# pga.net
KiCad netlist of a schematic drawn in Altium Designer
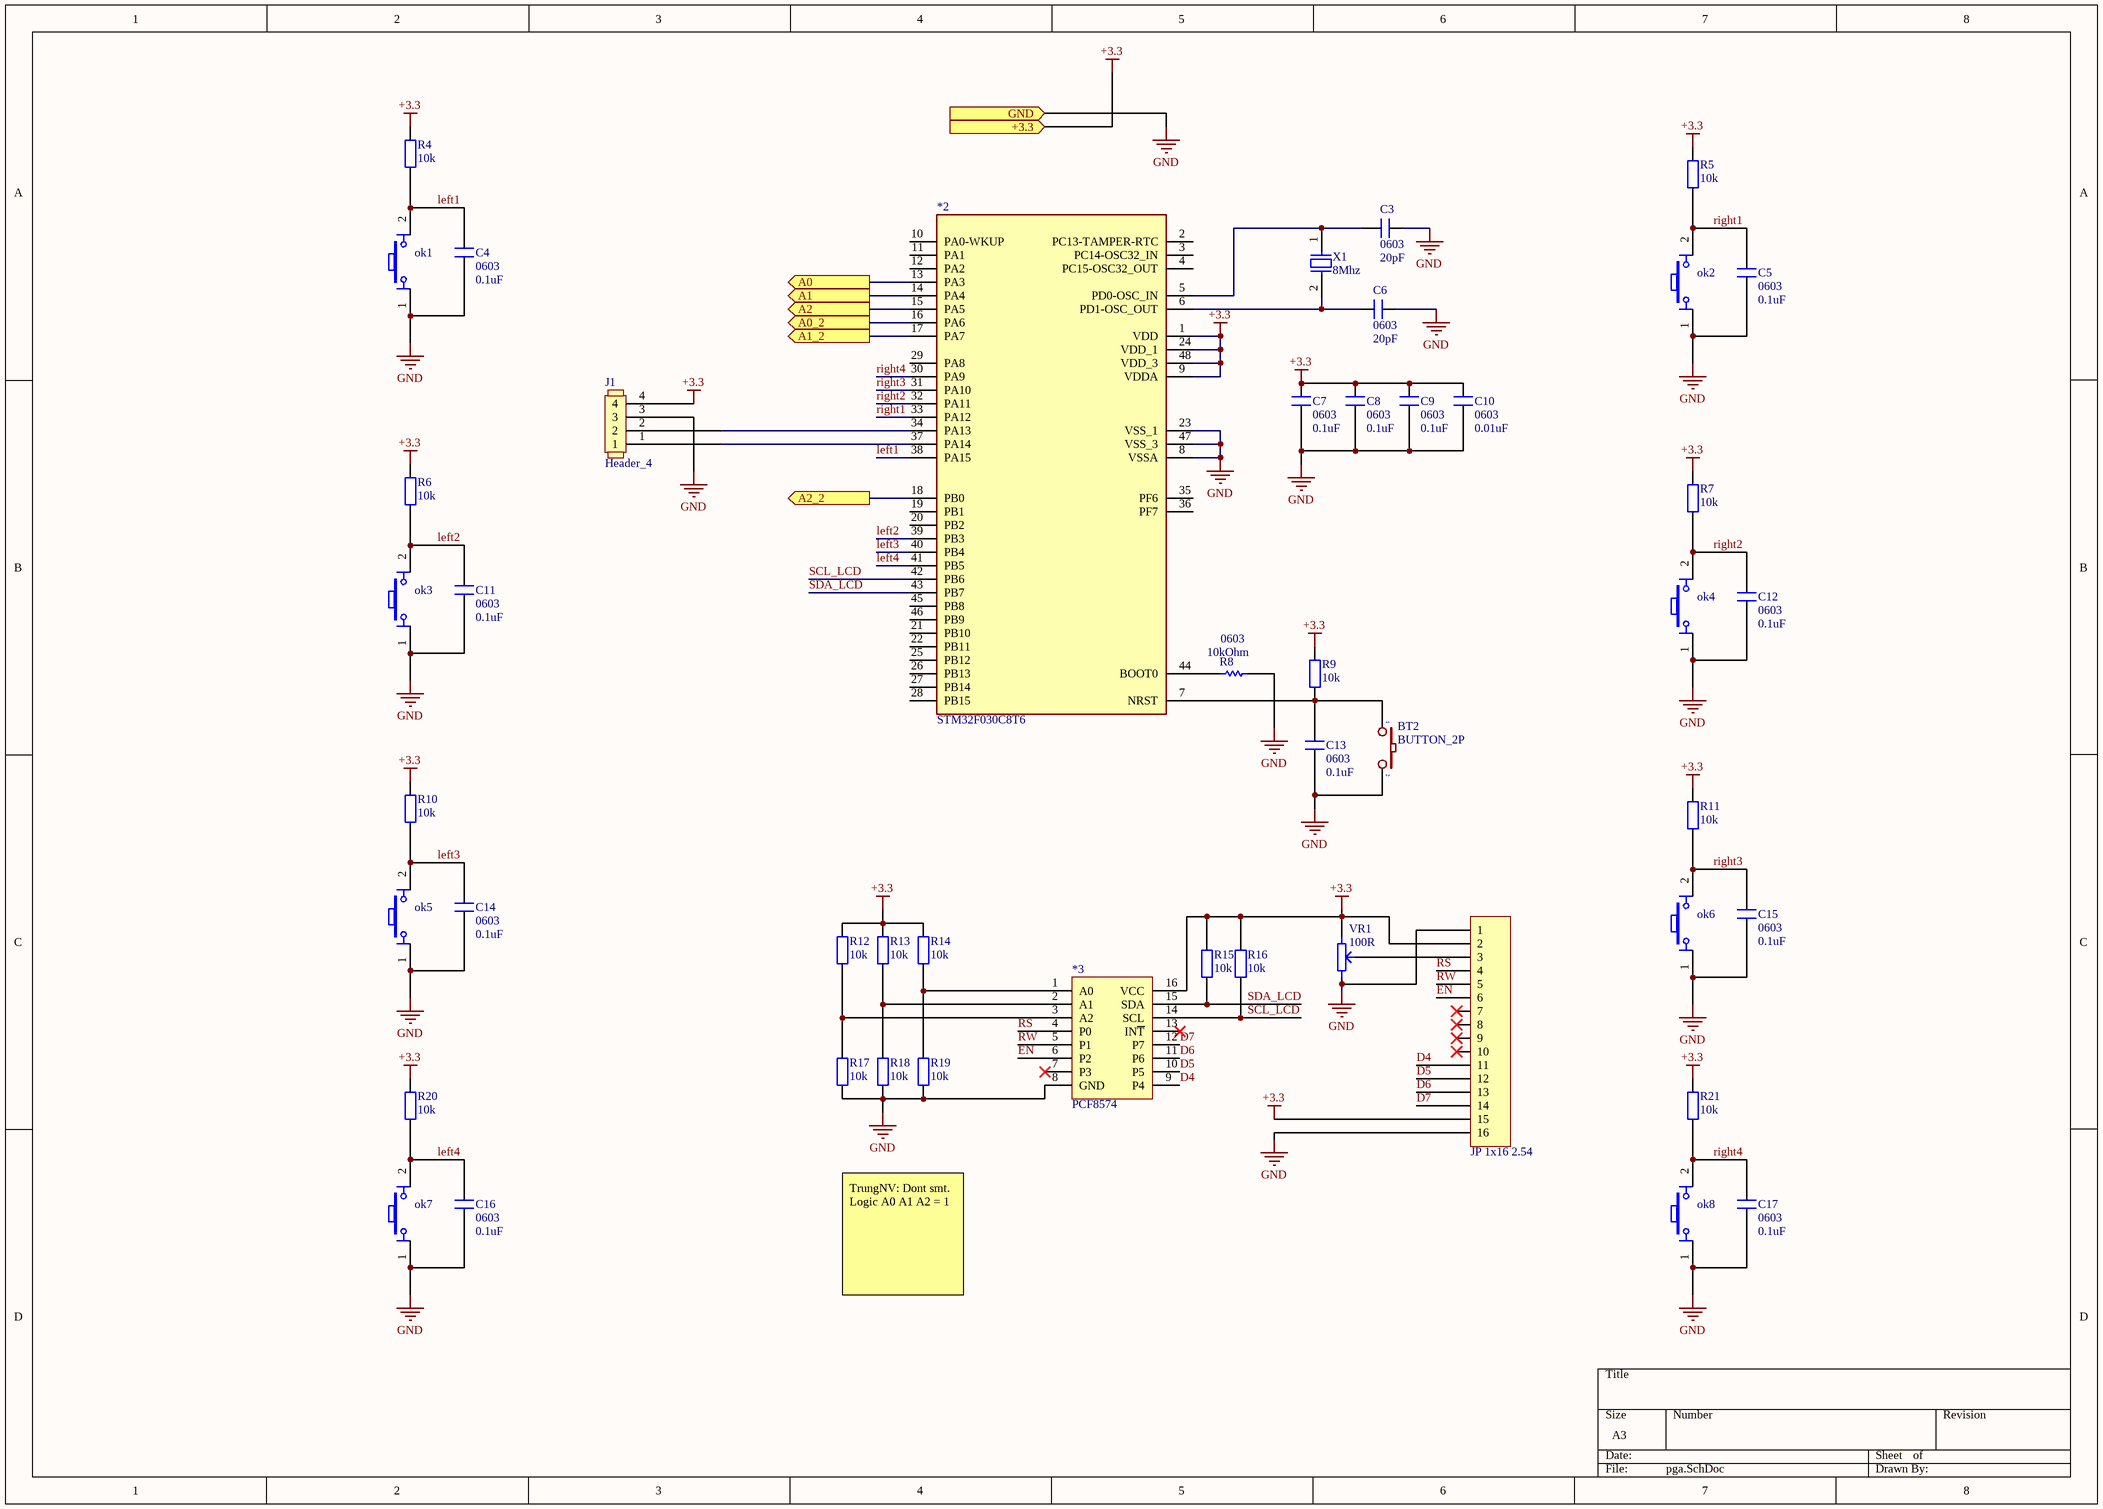
[diagram p0: pga.SchDoc]

(export (version "E")
  (design (tool "Eeschema 10.0.6"))
  (components
    (comp (ref "*2")
      (value "STM32F030C8T6")
      (footprint "STM32_LQPF48")
      (libsource (lib "TrungVan_Lib") (part "STM32F030C8T6"))
    )
    (comp (ref "*3")
      (value "PCF8574")
      (footprint "SOIC 16")
      (libsource (lib "TrungVan_Lib") (part "PCF8574"))
    )
    (comp (ref "BT2")
      (value "BUTTON_2P")
      (footprint "BUTTON_2P_SMD")
      (fields (field (name "MANUFACTURER") "C&K") (field (name "PART NUMBER") "PTS636 SM25F SMTR LFS"))
      (libsource (lib "S2000_Electromechanical") (part "BUTTON_2P"))
    )
    (comp (ref "C3")
      (value "0603")
      (footprint "C_0603")
      (description "Ceramic Capacitor 0603  (+-10% TH)/(+10%SMD)")
      (fields
        (field (name "MANUFACTURER") "Murata Electronics")
        (field (name "PART NUMBER") "GRM1885C1H180JA01J")
        (field (name "ALTIUM_VALUE") "20pF")
      )
      (libsource (lib "S1200_Capacitor") (part "Cap_Cer_0603_18pF"))
    )
    (comp (ref "C4")
      (value "0603")
      (footprint "C_0603")
      (description "Ceramic Capacitor 0603  (+-10% TH)/(+10%SMD)")
      (fields
        (field (name "MANUFACTURER") "Murata Electronics")
        (field (name "PART NUMBER") "GRM188R71H104KA93D")
        (field (name "ALTIUM_VALUE") "0.1uF")
      )
      (libsource (lib "S1200_Capacitor") (part "Cap_Cer_0603_0.1uF_50V"))
    )
    (comp (ref "C5")
      (value "0603")
      (footprint "C_0603")
      (description "Ceramic Capacitor 0603  (+-10% TH)/(+10%SMD)")
      (fields
        (field (name "MANUFACTURER") "Murata Electronics")
        (field (name "PART NUMBER") "GRM188R71H104KA93D")
        (field (name "ALTIUM_VALUE") "0.1uF")
      )
      (libsource (lib "S1200_Capacitor") (part "Cap_Cer_0603_0.1uF_50V"))
    )
    (comp (ref "C6")
      (value "0603")
      (footprint "C_0603")
      (description "Ceramic Capacitor 0603  (+-10% TH)/(+10%SMD)")
      (fields
        (field (name "MANUFACTURER") "Murata Electronics")
        (field (name "PART NUMBER") "GCM188R91E104KA37J")
        (field (name "ALTIUM_VALUE") "20pF")
      )
      (libsource (lib "S1200_Capacitor") (part "Cap_Cer_0603_0.1uF_25V"))
    )
    (comp (ref "C7")
      (value "0603")
      (footprint "C_0603")
      (description "Ceramic Capacitor 0603  (+-10% TH)/(+10%SMD)")
      (fields
        (field (name "MANUFACTURER") "Murata Electronics")
        (field (name "PART NUMBER") "GCM188R91E104KA37J")
        (field (name "ALTIUM_VALUE") "0.1uF")
      )
      (libsource (lib "S1200_Capacitor") (part "Cap_Cer_0603_0.1uF_25V"))
    )
    (comp (ref "C8")
      (value "0603")
      (footprint "C_0603")
      (description "Ceramic Capacitor 0603  (+-10% TH)/(+10%SMD)")
      (fields
        (field (name "MANUFACTURER") "Murata Electronics")
        (field (name "PART NUMBER") "GCM188R91E104KA37J")
        (field (name "ALTIUM_VALUE") "0.1uF")
      )
      (libsource (lib "S1200_Capacitor") (part "Cap_Cer_0603_0.1uF_25V"))
    )
    (comp (ref "C9")
      (value "0603")
      (footprint "C_0603")
      (description "Ceramic Capacitor 0603  (+-10% TH)/(+10%SMD)")
      (fields
        (field (name "MANUFACTURER") "Murata Electronics")
        (field (name "PART NUMBER") "GCM188R91E104KA37J")
        (field (name "ALTIUM_VALUE") "0.1uF")
      )
      (libsource (lib "S1200_Capacitor") (part "Cap_Cer_0603_0.1uF_25V"))
    )
    (comp (ref "C10")
      (value "0603")
      (footprint "C_0603")
      (description "Ceramic Capacitor 0603  (+-10% TH)/(+10%SMD)")
      (fields
        (field (name "MANUFACTURER") "Murata Electronics")
        (field (name "PART NUMBER") "GCM188R91E104KA37J")
        (field (name "ALTIUM_VALUE") "0.01uF")
      )
      (libsource (lib "S1200_Capacitor") (part "Cap_Cer_0603_0.1uF_25V"))
    )
    (comp (ref "C11")
      (value "0603")
      (footprint "C_0603")
      (description "Ceramic Capacitor 0603  (+-10% TH)/(+10%SMD)")
      (fields
        (field (name "MANUFACTURER") "Murata Electronics")
        (field (name "PART NUMBER") "GRM188R71H104KA93D")
        (field (name "ALTIUM_VALUE") "0.1uF")
      )
      (libsource (lib "S1200_Capacitor") (part "Cap_Cer_0603_0.1uF_50V"))
    )
    (comp (ref "C12")
      (value "0603")
      (footprint "C_0603")
      (description "Ceramic Capacitor 0603  (+-10% TH)/(+10%SMD)")
      (fields
        (field (name "MANUFACTURER") "Murata Electronics")
        (field (name "PART NUMBER") "GRM188R71H104KA93D")
        (field (name "ALTIUM_VALUE") "0.1uF")
      )
      (libsource (lib "S1200_Capacitor") (part "Cap_Cer_0603_0.1uF_50V"))
    )
    (comp (ref "C13")
      (value "0603")
      (footprint "C_0603")
      (description "Ceramic Capacitor 0603  (+-10% TH)/(+10%SMD)")
      (fields
        (field (name "MANUFACTURER") "Murata Electronics")
        (field (name "PART NUMBER") "GCM188R91E104KA37J")
        (field (name "ALTIUM_VALUE") "0.1uF")
      )
      (libsource (lib "S1200_Capacitor") (part "Cap_Cer_0603_0.1uF_25V"))
    )
    (comp (ref "C14")
      (value "0603")
      (footprint "C_0603")
      (description "Ceramic Capacitor 0603  (+-10% TH)/(+10%SMD)")
      (fields
        (field (name "MANUFACTURER") "Murata Electronics")
        (field (name "PART NUMBER") "GRM188R71H104KA93D")
        (field (name "ALTIUM_VALUE") "0.1uF")
      )
      (libsource (lib "S1200_Capacitor") (part "Cap_Cer_0603_0.1uF_50V"))
    )
    (comp (ref "C15")
      (value "0603")
      (footprint "C_0603")
      (description "Ceramic Capacitor 0603  (+-10% TH)/(+10%SMD)")
      (fields
        (field (name "MANUFACTURER") "Murata Electronics")
        (field (name "PART NUMBER") "GRM188R71H104KA93D")
        (field (name "ALTIUM_VALUE") "0.1uF")
      )
      (libsource (lib "S1200_Capacitor") (part "Cap_Cer_0603_0.1uF_50V"))
    )
    (comp (ref "C16")
      (value "0603")
      (footprint "C_0603")
      (description "Ceramic Capacitor 0603  (+-10% TH)/(+10%SMD)")
      (fields
        (field (name "MANUFACTURER") "Murata Electronics")
        (field (name "PART NUMBER") "GRM188R71H104KA93D")
        (field (name "ALTIUM_VALUE") "0.1uF")
      )
      (libsource (lib "S1200_Capacitor") (part "Cap_Cer_0603_0.1uF_50V"))
    )
    (comp (ref "C17")
      (value "0603")
      (footprint "C_0603")
      (description "Ceramic Capacitor 0603  (+-10% TH)/(+10%SMD)")
      (fields
        (field (name "MANUFACTURER") "Murata Electronics")
        (field (name "PART NUMBER") "GRM188R71H104KA93D")
        (field (name "ALTIUM_VALUE") "0.1uF")
      )
      (libsource (lib "S1200_Capacitor") (part "Cap_Cer_0603_0.1uF_50V"))
    )
    (comp (ref "J1")
      (value "Header_4")
      (footprint "HEADER_4_2P54_SHROUDED")
      (libsource (lib "S1900_Connector") (part "Header_4"))
    )
    (comp (ref "JP2")
      (value "JP 1x16 2.54")
      (footprint "JP 1X16 DT")
      (description "Cắm")
      (libsource (lib "TrungVan_Lib") (part "JP 1x16 2.54 Duc Thang"))
    )
    (comp (ref "ok1")
      (value "Nut Nhan 4 Chan Cam 6x6")
      (footprint "Nut Nhan 4 Chan Cam 6x6")
      (description "Nut Nhan 4 Chan 6x6mm")
      (libsource (lib "TrungVan_Lib") (part "Nut Nhan 4 Chan Cam 6x6"))
    )
    (comp (ref "ok2")
      (value "Nut Nhan 4 Chan Cam 6x6")
      (footprint "Nut Nhan 4 Chan Cam 6x6")
      (description "Nut Nhan 4 Chan 6x6mm")
      (libsource (lib "TrungVan_Lib") (part "Nut Nhan 4 Chan Cam 6x6"))
    )
    (comp (ref "ok3")
      (value "Nut Nhan 4 Chan Cam 6x6")
      (footprint "Nut Nhan 4 Chan Cam 6x6")
      (description "Nut Nhan 4 Chan 6x6mm")
      (libsource (lib "TrungVan_Lib") (part "Nut Nhan 4 Chan Cam 6x6"))
    )
    (comp (ref "ok4")
      (value "Nut Nhan 4 Chan Cam 6x6")
      (footprint "Nut Nhan 4 Chan Cam 6x6")
      (description "Nut Nhan 4 Chan 6x6mm")
      (libsource (lib "TrungVan_Lib") (part "Nut Nhan 4 Chan Cam 6x6"))
    )
    (comp (ref "ok5")
      (value "Nut Nhan 4 Chan Cam 6x6")
      (footprint "Nut Nhan 4 Chan Cam 6x6")
      (description "Nut Nhan 4 Chan 6x6mm")
      (libsource (lib "TrungVan_Lib") (part "Nut Nhan 4 Chan Cam 6x6"))
    )
    (comp (ref "ok6")
      (value "Nut Nhan 4 Chan Cam 6x6")
      (footprint "Nut Nhan 4 Chan Cam 6x6")
      (description "Nut Nhan 4 Chan 6x6mm")
      (libsource (lib "TrungVan_Lib") (part "Nut Nhan 4 Chan Cam 6x6"))
    )
    (comp (ref "ok7")
      (value "Nut Nhan 4 Chan Cam 6x6")
      (footprint "Nut Nhan 4 Chan Cam 6x6")
      (description "Nut Nhan 4 Chan 6x6mm")
      (libsource (lib "TrungVan_Lib") (part "Nut Nhan 4 Chan Cam 6x6"))
    )
    (comp (ref "ok8")
      (value "Nut Nhan 4 Chan Cam 6x6")
      (footprint "Nut Nhan 4 Chan Cam 6x6")
      (description "Nut Nhan 4 Chan 6x6mm")
      (libsource (lib "TrungVan_Lib") (part "Nut Nhan 4 Chan Cam 6x6"))
    )
    (comp (ref "R4")
      (value "10k")
      (footprint "tro smd 0805")
      (description "Dán")
      (libsource (lib "TrungVan_Lib") (part "Tro 0805 1% 10k"))
    )
    (comp (ref "R5")
      (value "10k")
      (footprint "tro smd 0805")
      (description "Dán")
      (libsource (lib "TrungVan_Lib") (part "Tro 0805 1% 10k"))
    )
    (comp (ref "R6")
      (value "10k")
      (footprint "tro smd 0805")
      (description "Dán")
      (libsource (lib "TrungVan_Lib") (part "Tro 0805 1% 10k"))
    )
    (comp (ref "R7")
      (value "10k")
      (footprint "tro smd 0805")
      (description "Dán")
      (libsource (lib "TrungVan_Lib") (part "Tro 0805 1% 10k"))
    )
    (comp (ref "R8")
      (value "0603")
      (footprint "R_0603")
      (description "RES 10K OHM 1% 1/10W 0603")
      (fields
        (field (name "MANUFACTURER") "YAGEO")
        (field (name "PART NUMBER") "RC0603FR-7W10KL")
        (field (name "ALTIUM_VALUE") "10kOhm")
      )
      (libsource (lib "S1100_Resistor_FerriteBead") (part "Resistor_0603_10kOhm 1%"))
    )
    (comp (ref "R9")
      (value "10k")
      (footprint "tro smd 0805")
      (description "Dán")
      (libsource (lib "TrungVan_Lib") (part "Tro 0805 1% 10k"))
    )
    (comp (ref "R10")
      (value "10k")
      (footprint "tro smd 0805")
      (description "Dán")
      (libsource (lib "TrungVan_Lib") (part "Tro 0805 1% 10k"))
    )
    (comp (ref "R11")
      (value "10k")
      (footprint "tro smd 0805")
      (description "Dán")
      (libsource (lib "TrungVan_Lib") (part "Tro 0805 1% 10k"))
    )
    (comp (ref "R12")
      (value "10k")
      (footprint "tro smd 0805")
      (description "Dán")
      (libsource (lib "TrungVan_Lib") (part "Tro 0805 1% 10k"))
    )
    (comp (ref "R13")
      (value "10k")
      (footprint "tro smd 0805")
      (description "Dán")
      (libsource (lib "TrungVan_Lib") (part "Tro 0805 1% 10k"))
    )
    (comp (ref "R14")
      (value "10k")
      (footprint "tro smd 0805")
      (description "Dán")
      (libsource (lib "TrungVan_Lib") (part "Tro 0805 1% 10k"))
    )
    (comp (ref "R15")
      (value "10k")
      (footprint "tro smd 0805")
      (description "Dán")
      (libsource (lib "TrungVan_Lib") (part "Tro 0805 1% 10k"))
    )
    (comp (ref "R16")
      (value "10k")
      (footprint "tro smd 0805")
      (description "Dán")
      (libsource (lib "TrungVan_Lib") (part "Tro 0805 1% 10k"))
    )
    (comp (ref "R17")
      (value "10k")
      (footprint "tro smd 0805")
      (description "Dán")
      (libsource (lib "TrungVan_Lib") (part "Tro 0805 1% 10k"))
    )
    (comp (ref "R18")
      (value "10k")
      (footprint "tro smd 0805")
      (description "Dán")
      (libsource (lib "TrungVan_Lib") (part "Tro 0805 1% 10k"))
    )
    (comp (ref "R19")
      (value "10k")
      (footprint "tro smd 0805")
      (description "Dán")
      (libsource (lib "TrungVan_Lib") (part "Tro 0805 1% 10k"))
    )
    (comp (ref "R20")
      (value "10k")
      (footprint "tro smd 0805")
      (description "Dán")
      (libsource (lib "TrungVan_Lib") (part "Tro 0805 1% 10k"))
    )
    (comp (ref "R21")
      (value "10k")
      (footprint "tro smd 0805")
      (description "Dán")
      (libsource (lib "TrungVan_Lib") (part "Tro 0805 1% 10k"))
    )
    (comp (ref "VR1")
      (value "100R")
      (footprint "Bien Tro Tam Giac Dung")
      (description "Cắm")
      (libsource (lib "TrungVan_Lib") (part "Bien tro tam giac 100R Dung"))
    )
    (comp (ref "X1")
      (value "8Mhz")
      (footprint "XTAL_SMD_3P5")
      (description "Use for 8Mhz")
      (fields (field (name "MANUFACTURER") "WTL") (field (name "PART NUMBER") "WTL5G11651"))
      (libsource (lib "S1600_Crystal_Oscillator") (part "Xtal_2P_SMD_5P0X3P5_8Mhz"))
    )
  )
  (nets
    (net (code "1") (name "+3.3") (class "Default")
      (node (ref "*2") (pin "1") (pinfunction "VDD_1") (pintype "passive"))
      (node (ref "*2") (pin "24") (pinfunction "VDD_1_24") (pintype "passive"))
      (node (ref "*2") (pin "48") (pinfunction "VDD_3_48") (pintype "passive"))
      (node (ref "*2") (pin "9") (pinfunction "VDDA_9") (pintype "passive"))
      (node (ref "*3") (pin "16") (pinfunction "VCC_16") (pintype "passive"))
      (node (ref "C10") (pin "2") (pinfunction "2_2") (pintype "passive"))
      (node (ref "C7") (pin "2") (pinfunction "2_2") (pintype "passive"))
      (node (ref "C8") (pin "2") (pinfunction "2_2") (pintype "passive"))
      (node (ref "C9") (pin "2") (pinfunction "2_2") (pintype "passive"))
      (node (ref "J1") (pin "4") (pinfunction "4_4") (pintype "passive"))
      (node (ref "JP2") (pin "15") (pinfunction "15_15") (pintype "passive"))
      (node (ref "JP2") (pin "2") (pinfunction "2_2") (pintype "passive"))
      (node (ref "R10") (pin "2") (pinfunction "2_2") (pintype "passive"))
      (node (ref "R11") (pin "2") (pinfunction "2_2") (pintype "passive"))
      (node (ref "R12") (pin "2") (pinfunction "2_2") (pintype "passive"))
      (node (ref "R13") (pin "2") (pinfunction "2_2") (pintype "passive"))
      (node (ref "R14") (pin "2") (pinfunction "2_2") (pintype "passive"))
      (node (ref "R15") (pin "2") (pinfunction "2_2") (pintype "passive"))
      (node (ref "R16") (pin "2") (pinfunction "2_2") (pintype "passive"))
      (node (ref "R20") (pin "2") (pinfunction "2_2") (pintype "passive"))
      (node (ref "R21") (pin "2") (pinfunction "2_2") (pintype "passive"))
      (node (ref "R4") (pin "2") (pinfunction "2_2") (pintype "passive"))
      (node (ref "R5") (pin "2") (pinfunction "2_2") (pintype "passive"))
      (node (ref "R6") (pin "2") (pinfunction "2_2") (pintype "passive"))
      (node (ref "R7") (pin "2") (pinfunction "2_2") (pintype "passive"))
      (node (ref "R9") (pin "2") (pinfunction "2_2") (pintype "passive"))
      (node (ref "VR1") (pin "1") (pinfunction "1_1") (pintype "passive"))
    )
    (net (code "2") (name "/A0") (class "Default")
      (node (ref "*2") (pin "13") (pinfunction "PA3_13") (pintype "passive"))
    )
    (net (code "3") (name "/A0_2") (class "Default")
      (node (ref "*2") (pin "16") (pinfunction "PA6_16") (pintype "passive"))
    )
    (net (code "4") (name "/A1") (class "Default")
      (node (ref "*2") (pin "14") (pinfunction "PA4_14") (pintype "passive"))
    )
    (net (code "5") (name "/A1_2") (class "Default")
      (node (ref "*2") (pin "17") (pinfunction "PA7_17") (pintype "passive"))
    )
    (net (code "6") (name "/A2") (class "Default")
      (node (ref "*2") (pin "15") (pinfunction "PA5_15") (pintype "passive"))
    )
    (net (code "7") (name "/A2_2") (class "Default")
      (node (ref "*2") (pin "18") (pinfunction "PB0_18") (pintype "passive"))
    )
    (net (code "8") (name "/D4") (class "Default")
      (node (ref "*3") (pin "9") (pinfunction "P4_9") (pintype "passive"))
      (node (ref "JP2") (pin "11") (pinfunction "11_11") (pintype "passive"))
    )
    (net (code "9") (name "/D5") (class "Default")
      (node (ref "*3") (pin "10") (pinfunction "P5_10") (pintype "passive"))
      (node (ref "JP2") (pin "12") (pinfunction "12_12") (pintype "passive"))
    )
    (net (code "10") (name "/D6") (class "Default")
      (node (ref "*3") (pin "11") (pinfunction "P6_11") (pintype "passive"))
      (node (ref "JP2") (pin "13") (pinfunction "13_13") (pintype "passive"))
    )
    (net (code "11") (name "/D7") (class "Default")
      (node (ref "*3") (pin "12") (pinfunction "P7_12") (pintype "passive"))
      (node (ref "JP2") (pin "14") (pinfunction "14_14") (pintype "passive"))
    )
    (net (code "12") (name "/EN") (class "Default")
      (node (ref "*3") (pin "6") (pinfunction "P2_6") (pintype "passive"))
      (node (ref "JP2") (pin "6") (pinfunction "6_6") (pintype "passive"))
    )
    (net (code "13") (name "/RS") (class "Default")
      (node (ref "*3") (pin "4") (pinfunction "P0_4") (pintype "passive"))
      (node (ref "JP2") (pin "4") (pinfunction "4_4") (pintype "passive"))
    )
    (net (code "14") (name "/RW") (class "Default")
      (node (ref "*3") (pin "5") (pinfunction "P1_5") (pintype "passive"))
      (node (ref "JP2") (pin "5") (pinfunction "5_5") (pintype "passive"))
    )
    (net (code "15") (name "/SCL_LCD") (class "Default")
      (node (ref "*2") (pin "42") (pinfunction "PB6_42") (pintype "passive"))
      (node (ref "*3") (pin "14") (pinfunction "SCL_14") (pintype "passive"))
      (node (ref "R16") (pin "1") (pinfunction "1_1") (pintype "passive"))
    )
    (net (code "16") (name "/SDA_LCD") (class "Default")
      (node (ref "*2") (pin "43") (pinfunction "PB7_43") (pintype "passive"))
      (node (ref "*3") (pin "15") (pinfunction "SDA_15") (pintype "passive"))
      (node (ref "R15") (pin "1") (pinfunction "1_1") (pintype "passive"))
    )
    (net (code "17") (name "/left1") (class "Default")
      (node (ref "*2") (pin "38") (pinfunction "PA15_38") (pintype "passive"))
      (node (ref "C4") (pin "2") (pinfunction "2_2") (pintype "passive"))
      (node (ref "R4") (pin "1") (pinfunction "1_1") (pintype "passive"))
      (node (ref "ok1") (pin "2") (pintype "passive"))
    )
    (net (code "18") (name "/left2") (class "Default")
      (node (ref "*2") (pin "39") (pinfunction "PB3_39") (pintype "passive"))
      (node (ref "C11") (pin "2") (pinfunction "2_2") (pintype "passive"))
      (node (ref "R6") (pin "1") (pinfunction "1_1") (pintype "passive"))
      (node (ref "ok3") (pin "2") (pintype "passive"))
    )
    (net (code "19") (name "/left3") (class "Default")
      (node (ref "*2") (pin "40") (pinfunction "PB4_40") (pintype "passive"))
      (node (ref "C14") (pin "2") (pinfunction "2_2") (pintype "passive"))
      (node (ref "R10") (pin "1") (pinfunction "1_1") (pintype "passive"))
      (node (ref "ok5") (pin "2") (pintype "passive"))
    )
    (net (code "20") (name "/left4") (class "Default")
      (node (ref "*2") (pin "41") (pinfunction "PB5_41") (pintype "passive"))
      (node (ref "C16") (pin "2") (pinfunction "2_2") (pintype "passive"))
      (node (ref "R20") (pin "1") (pinfunction "1_1") (pintype "passive"))
      (node (ref "ok7") (pin "2") (pintype "passive"))
    )
    (net (code "21") (name "/right1") (class "Default")
      (node (ref "*2") (pin "33") (pinfunction "PA12_33") (pintype "passive"))
      (node (ref "C5") (pin "2") (pinfunction "2_2") (pintype "passive"))
      (node (ref "R5") (pin "1") (pinfunction "1_1") (pintype "passive"))
      (node (ref "ok2") (pin "2") (pintype "passive"))
    )
    (net (code "22") (name "/right2") (class "Default")
      (node (ref "*2") (pin "32") (pinfunction "PA11_32") (pintype "passive"))
      (node (ref "C12") (pin "2") (pinfunction "2_2") (pintype "passive"))
      (node (ref "R7") (pin "1") (pinfunction "1_1") (pintype "passive"))
      (node (ref "ok4") (pin "2") (pintype "passive"))
    )
    (net (code "23") (name "/right3") (class "Default")
      (node (ref "*2") (pin "31") (pinfunction "PA10_31") (pintype "passive"))
      (node (ref "C15") (pin "2") (pinfunction "2_2") (pintype "passive"))
      (node (ref "R11") (pin "1") (pinfunction "1_1") (pintype "passive"))
      (node (ref "ok6") (pin "2") (pintype "passive"))
    )
    (net (code "24") (name "/right4") (class "Default")
      (node (ref "*2") (pin "30") (pinfunction "PA9_30") (pintype "passive"))
      (node (ref "C17") (pin "2") (pinfunction "2_2") (pintype "passive"))
      (node (ref "R21") (pin "1") (pinfunction "1_1") (pintype "passive"))
      (node (ref "ok8") (pin "2") (pintype "passive"))
    )
    (net (code "25") (name "GND") (class "Default")
      (node (ref "*2") (pin "23") (pinfunction "VSS_1_23") (pintype "passive"))
      (node (ref "*2") (pin "47") (pinfunction "VSS_3_47") (pintype "passive"))
      (node (ref "*2") (pin "8") (pinfunction "VSSA_8") (pintype "passive"))
      (node (ref "*3") (pin "8") (pinfunction "GND_8") (pintype "passive"))
      (node (ref "BT2") (pin "2") (pinfunction "2_2") (pintype "passive"))
      (node (ref "C10") (pin "1") (pinfunction "1_1") (pintype "passive"))
      (node (ref "C11") (pin "1") (pinfunction "1_1") (pintype "passive"))
      (node (ref "C12") (pin "1") (pinfunction "1_1") (pintype "passive"))
      (node (ref "C13") (pin "1") (pinfunction "1_1") (pintype "passive"))
      (node (ref "C14") (pin "1") (pinfunction "1_1") (pintype "passive"))
      (node (ref "C15") (pin "1") (pinfunction "1_1") (pintype "passive"))
      (node (ref "C16") (pin "1") (pinfunction "1_1") (pintype "passive"))
      (node (ref "C17") (pin "1") (pinfunction "1_1") (pintype "passive"))
      (node (ref "C3") (pin "2") (pinfunction "2_2") (pintype "passive"))
      (node (ref "C4") (pin "1") (pinfunction "1_1") (pintype "passive"))
      (node (ref "C5") (pin "1") (pinfunction "1_1") (pintype "passive"))
      (node (ref "C6") (pin "2") (pinfunction "2_2") (pintype "passive"))
      (node (ref "C7") (pin "1") (pinfunction "1_1") (pintype "passive"))
      (node (ref "C8") (pin "1") (pinfunction "1_1") (pintype "passive"))
      (node (ref "C9") (pin "1") (pinfunction "1_1") (pintype "passive"))
      (node (ref "J1") (pin "3") (pinfunction "3_3") (pintype "passive"))
      (node (ref "JP2") (pin "1") (pinfunction "1_1") (pintype "passive"))
      (node (ref "JP2") (pin "16") (pinfunction "16_16") (pintype "passive"))
      (node (ref "R17") (pin "1") (pinfunction "1_1") (pintype "passive"))
      (node (ref "R18") (pin "1") (pinfunction "1_1") (pintype "passive"))
      (node (ref "R19") (pin "1") (pinfunction "1_1") (pintype "passive"))
      (node (ref "R8") (pin "2") (pinfunction "2_2") (pintype "passive"))
      (node (ref "VR1") (pin "3") (pinfunction "3_3") (pintype "passive"))
      (node (ref "ok1") (pin "1") (pintype "passive"))
      (node (ref "ok2") (pin "1") (pintype "passive"))
      (node (ref "ok3") (pin "1") (pintype "passive"))
      (node (ref "ok4") (pin "1") (pintype "passive"))
      (node (ref "ok5") (pin "1") (pintype "passive"))
      (node (ref "ok6") (pin "1") (pintype "passive"))
      (node (ref "ok7") (pin "1") (pintype "passive"))
      (node (ref "ok8") (pin "1") (pintype "passive"))
    )
    (net (code "26") (name "Net-(*2-BOOT0)") (class "Default")
      (node (ref "*2") (pin "44") (pinfunction "BOOT0_44") (pintype "passive"))
      (node (ref "R8") (pin "1") (pinfunction "1_1") (pintype "passive"))
    )
    (net (code "27") (name "Net-(*2-NRST)") (class "Default")
      (node (ref "*2") (pin "7") (pinfunction "NRST_7") (pintype "passive"))
      (node (ref "BT2") (pin "1") (pinfunction "1_1") (pintype "passive"))
      (node (ref "C13") (pin "2") (pinfunction "2_2") (pintype "passive"))
      (node (ref "R9") (pin "1") (pinfunction "1_1") (pintype "passive"))
    )
    (net (code "28") (name "Net-(*2-PA13)") (class "Default")
      (node (ref "*2") (pin "34") (pinfunction "PA13_34") (pintype "passive"))
      (node (ref "J1") (pin "2") (pinfunction "2_2") (pintype "passive"))
    )
    (net (code "29") (name "Net-(*2-PA14)") (class "Default")
      (node (ref "*2") (pin "37") (pinfunction "PA14_37") (pintype "passive"))
      (node (ref "J1") (pin "1") (pinfunction "1_1") (pintype "passive"))
    )
    (net (code "30") (name "Net-(*2-PD0-OSC_IN)") (class "Default")
      (node (ref "*2") (pin "5") (pinfunction "PD0-OSC_IN_5") (pintype "passive"))
      (node (ref "C3") (pin "1") (pinfunction "1_1") (pintype "passive"))
      (node (ref "X1") (pin "1") (pinfunction "1_1") (pintype "passive"))
    )
    (net (code "31") (name "Net-(*2-PD1-OSC_OUT)") (class "Default")
      (node (ref "*2") (pin "6") (pinfunction "PD1-OSC_OUT_6") (pintype "passive"))
      (node (ref "C6") (pin "1") (pinfunction "1_1") (pintype "passive"))
      (node (ref "X1") (pin "2") (pinfunction "2_2") (pintype "passive"))
    )
    (net (code "32") (name "Net-(*3-A0)") (class "Default")
      (node (ref "*3") (pin "1") (pinfunction "A0_1") (pintype "passive"))
      (node (ref "R14") (pin "1") (pinfunction "1_1") (pintype "passive"))
      (node (ref "R19") (pin "2") (pinfunction "2_2") (pintype "passive"))
    )
    (net (code "33") (name "Net-(*3-A1)") (class "Default")
      (node (ref "*3") (pin "2") (pinfunction "A1_2") (pintype "passive"))
      (node (ref "R13") (pin "1") (pinfunction "1_1") (pintype "passive"))
      (node (ref "R18") (pin "2") (pinfunction "2_2") (pintype "passive"))
    )
    (net (code "34") (name "Net-(*3-A2)") (class "Default")
      (node (ref "*3") (pin "3") (pinfunction "A2_3") (pintype "passive"))
      (node (ref "R12") (pin "1") (pinfunction "1_1") (pintype "passive"))
      (node (ref "R17") (pin "2") (pinfunction "2_2") (pintype "passive"))
    )
    (net (code "35") (name "Net-(JP2-Pad3)") (class "Default")
      (node (ref "JP2") (pin "3") (pinfunction "3_3") (pintype "passive"))
      (node (ref "VR1") (pin "2") (pinfunction "2_2") (pintype "passive"))
    )
    (net (code "36") (name "unconnected-(*2-PA0-WKUP-Pad10)") (class "Default")
      (node (ref "*2") (pin "10") (pinfunction "PA0-WKUP_10") (pintype "passive"))
    )
    (net (code "37") (name "unconnected-(*2-PA1-Pad11)") (class "Default")
      (node (ref "*2") (pin "11") (pinfunction "PA1_11") (pintype "passive"))
    )
    (net (code "38") (name "unconnected-(*2-PA2-Pad12)") (class "Default")
      (node (ref "*2") (pin "12") (pinfunction "PA2_12") (pintype "passive"))
    )
    (net (code "39") (name "unconnected-(*2-PA8-Pad29)") (class "Default")
      (node (ref "*2") (pin "29") (pinfunction "PA8_29") (pintype "passive"))
    )
    (net (code "40") (name "unconnected-(*2-PB1-Pad19)") (class "Default")
      (node (ref "*2") (pin "19") (pinfunction "PB1_19") (pintype "passive"))
    )
    (net (code "41") (name "unconnected-(*2-PB2-Pad20)") (class "Default")
      (node (ref "*2") (pin "20") (pinfunction "PB2_20") (pintype "passive"))
    )
    (net (code "42") (name "unconnected-(*2-PB8-Pad45)") (class "Default")
      (node (ref "*2") (pin "45") (pinfunction "PB8_45") (pintype "passive"))
    )
    (net (code "43") (name "unconnected-(*2-PB9-Pad46)") (class "Default")
      (node (ref "*2") (pin "46") (pinfunction "PB9_46") (pintype "passive"))
    )
    (net (code "44") (name "unconnected-(*2-PB10-Pad21)") (class "Default")
      (node (ref "*2") (pin "21") (pinfunction "PB10_21") (pintype "passive"))
    )
    (net (code "45") (name "unconnected-(*2-PB11-Pad22)") (class "Default")
      (node (ref "*2") (pin "22") (pinfunction "PB11_22") (pintype "passive"))
    )
    (net (code "46") (name "unconnected-(*2-PB12-Pad25)") (class "Default")
      (node (ref "*2") (pin "25") (pinfunction "PB12_25") (pintype "passive"))
    )
    (net (code "47") (name "unconnected-(*2-PB13-Pad26)") (class "Default")
      (node (ref "*2") (pin "26") (pinfunction "PB13_26") (pintype "passive"))
    )
    (net (code "48") (name "unconnected-(*2-PB14-Pad27)") (class "Default")
      (node (ref "*2") (pin "27") (pinfunction "PB14_27") (pintype "passive"))
    )
    (net (code "49") (name "unconnected-(*2-PB15-Pad28)") (class "Default")
      (node (ref "*2") (pin "28") (pinfunction "PB15_28") (pintype "passive"))
    )
    (net (code "50") (name "unconnected-(*2-PC13-TAMPER-RTC-Pad2)") (class "Default")
      (node (ref "*2") (pin "2") (pinfunction "PC13-TAMPER-RTC_2") (pintype "passive"))
    )
    (net (code "51") (name "unconnected-(*2-PC14-OSC32_IN-Pad3)") (class "Default")
      (node (ref "*2") (pin "3") (pinfunction "PC14-OSC32_IN_3") (pintype "passive"))
    )
    (net (code "52") (name "unconnected-(*2-PC15-OSC32_OUT-Pad4)") (class "Default")
      (node (ref "*2") (pin "4") (pinfunction "PC15-OSC32_OUT_4") (pintype "passive"))
    )
    (net (code "53") (name "unconnected-(*2-PF6-Pad35)") (class "Default")
      (node (ref "*2") (pin "35") (pinfunction "PF6_35") (pintype "passive"))
    )
    (net (code "54") (name "unconnected-(*2-PF7-Pad36)") (class "Default")
      (node (ref "*2") (pin "36") (pinfunction "PF7_36") (pintype "passive"))
    )
    (net (code "55") (name "unconnected-(*3-IN~{T}-Pad13)") (class "Default")
      (node (ref "*3") (pin "13") (pinfunction "IN~{T}_13") (pintype "passive+no_connect"))
    )
    (net (code "56") (name "unconnected-(*3-P3-Pad7)") (class "Default")
      (node (ref "*3") (pin "7") (pinfunction "P3_7") (pintype "passive+no_connect"))
    )
    (net (code "57") (name "unconnected-(JP2-Pad7)") (class "Default")
      (node (ref "JP2") (pin "7") (pinfunction "7_7") (pintype "passive+no_connect"))
    )
    (net (code "58") (name "unconnected-(JP2-Pad8)") (class "Default")
      (node (ref "JP2") (pin "8") (pinfunction "8_8") (pintype "passive+no_connect"))
    )
    (net (code "59") (name "unconnected-(JP2-Pad9)") (class "Default")
      (node (ref "JP2") (pin "9") (pinfunction "9_9") (pintype "passive+no_connect"))
    )
    (net (code "60") (name "unconnected-(JP2-Pad10)") (class "Default")
      (node (ref "JP2") (pin "10") (pinfunction "10_10") (pintype "passive+no_connect"))
    )
  )
)
